# 09.net
KiCad netlist of a schematic drawn in Altium Designer
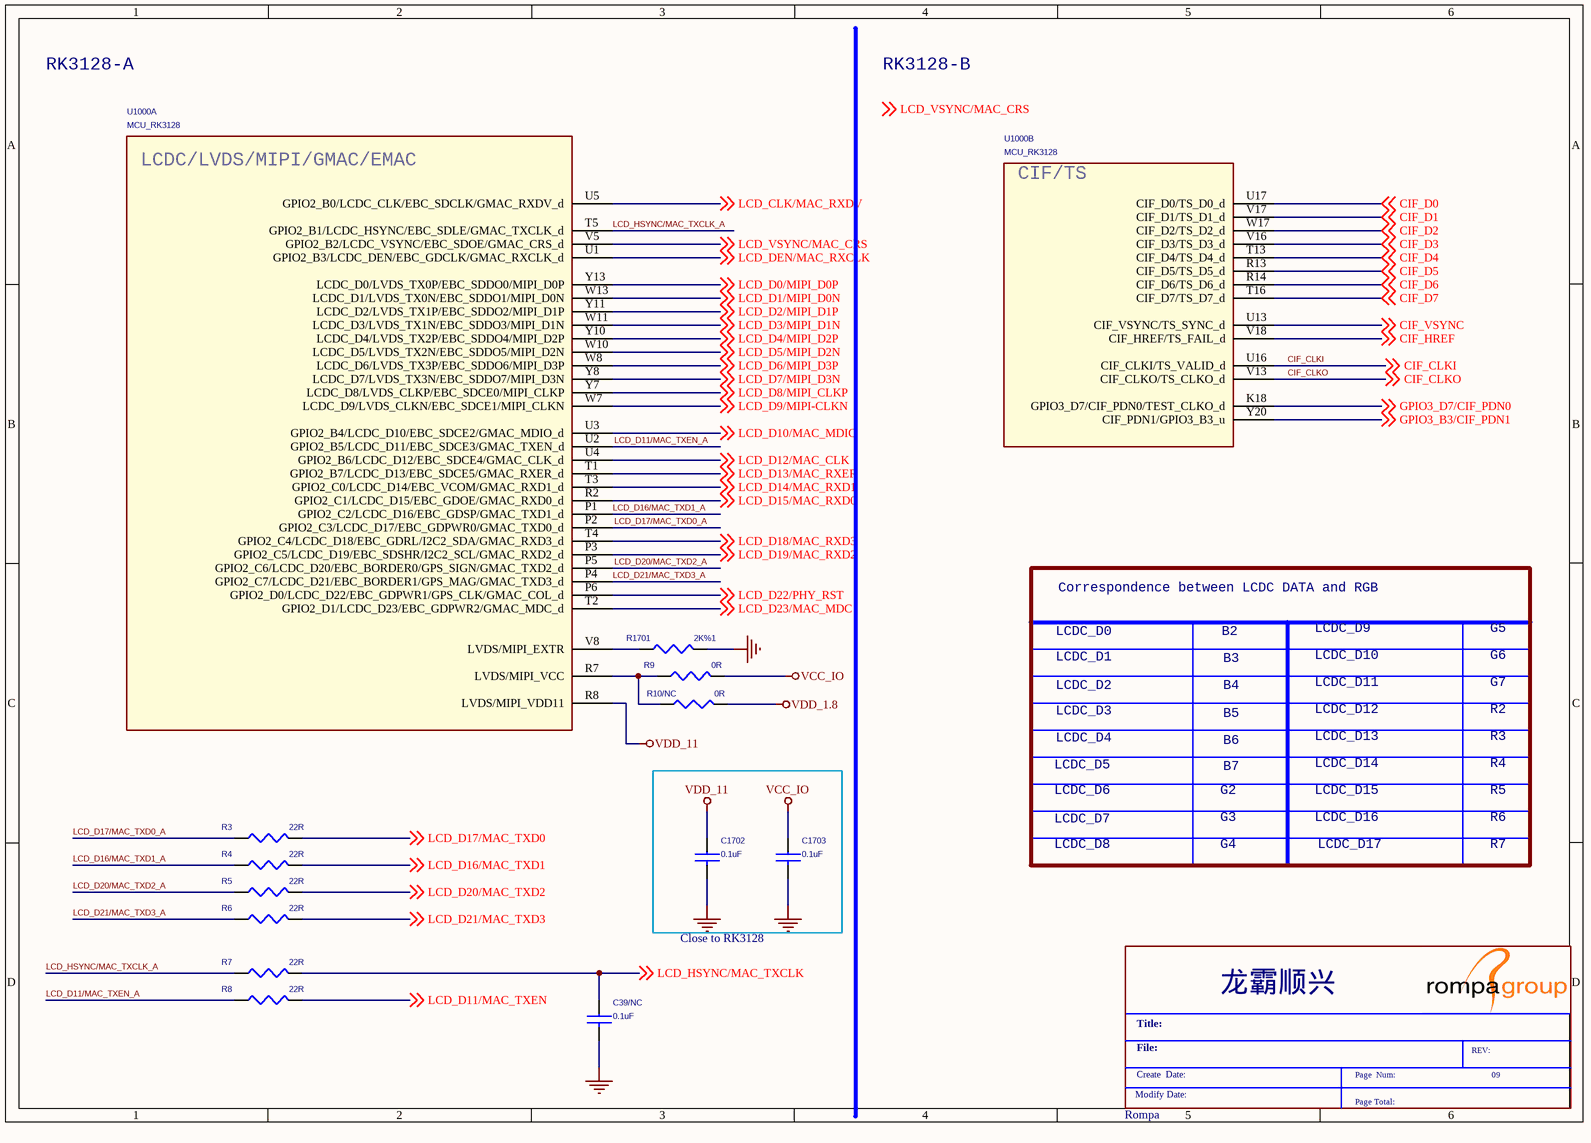
[diagram p0: 09.SchDoc]

(export (version "E")
  (design (tool "Eeschema 10.0.6"))
  (components
    (comp (ref "*")
      (value "Rompa")
      (fields (field (name "SCHEMATIC PAGE NUMBER") "09"))
      (libsource (lib "RK3128_BETA_V03_20151231_Library") (part "Rompa"))
    )
    (comp (ref "C39/NC")
      (value "0.1uF")
      (footprint "C0402")
      (description "RoHS CHIP CAP 0.1uF +10/-10% X7R")
      (libsource (lib "*") (part "CAP NP"))
    )
    (comp (ref "C1702")
      (value "0.1uF")
      (footprint "C0402")
      (description "RoHS CHIP CAP 0.1uF +10/-10% X7R")
      (libsource (lib "*") (part "CAP NP"))
    )
    (comp (ref "C1703")
      (value "0.1uF")
      (footprint "C0402")
      (description "RoHS CHIP CAP 0.1uF +10/-10% X7R")
      (libsource (lib "*") (part "CAP NP"))
    )
    (comp (ref "R3")
      (value "22R")
      (footprint "R0402")
      (description "ROHS CHIP RES 4.7K 1/16W 5%")
      (libsource (lib "*") (part "RES 1B"))
    )
    (comp (ref "R4")
      (value "22R")
      (footprint "R0402")
      (description "ROHS CHIP RES 4.7K 1/16W 5%")
      (libsource (lib "*") (part "RES 1B"))
    )
    (comp (ref "R5")
      (value "22R")
      (footprint "R0402")
      (description "ROHS CHIP RES 4.7K 1/16W 5%")
      (libsource (lib "*") (part "RES 1B"))
    )
    (comp (ref "R6")
      (value "22R")
      (footprint "R0402")
      (description "ROHS CHIP RES 4.7K 1/16W 5%")
      (libsource (lib "*") (part "RES 1B"))
    )
    (comp (ref "R7")
      (value "22R")
      (footprint "R0402")
      (description "ROHS CHIP RES 4.7K 1/16W 5%")
      (libsource (lib "*") (part "RES 1B"))
    )
    (comp (ref "R8")
      (value "22R")
      (footprint "R0402")
      (description "ROHS CHIP RES 4.7K 1/16W 5%")
      (libsource (lib "*") (part "RES 1B"))
    )
    (comp (ref "R9")
      (value "0R")
      (footprint "R0402")
      (description "ROHS CHIP RES 4.7K 1/16W 5%")
      (libsource (lib "*") (part "RES 1B"))
    )
    (comp (ref "R10/NC")
      (value "0R")
      (footprint "R0402")
      (description "NC/ 0R")
      (libsource (lib "*") (part "RES 1B"))
    )
    (comp (ref "R1701")
      (value "2K%1")
      (footprint "R0402")
      (description "ROHS CHIP RES 4.7K 1/16W 5%")
      (libsource (lib "*") (part "RES 1B"))
    )
    (comp (ref "U1000")
      (value "MCU_RK3128")
      (footprint "BGA316-14X14-0.65")
      (libsource (lib "*") (part "MCU_RK3128"))
    )
  )
  (nets
    (net (code "1") (name "/LCD_D11{slash}MAC_TXEN_A") (class "Default")
      (node (ref "R8") (pin "1") (pinfunction "1_1") (pintype "passive"))
      (node (ref "U1000") (pin "U2") (pinfunction "GPIO2_B5/LCDC_D11/EBC_SDCE3/GMAC_TXEN_d_U2") (pintype "passive"))
    )
    (net (code "2") (name "/LCD_D16{slash}MAC_TXD1_A") (class "Default")
      (node (ref "R4") (pin "1") (pinfunction "1_1") (pintype "passive"))
      (node (ref "U1000") (pin "P1") (pinfunction "GPIO2_C2/LCDC_D16/EBC_GDSP/GMAC_TXD1_d_P1") (pintype "passive"))
    )
    (net (code "3") (name "/LCD_D17{slash}MAC_TXD0_A") (class "Default")
      (node (ref "R3") (pin "1") (pinfunction "1_1") (pintype "passive"))
      (node (ref "U1000") (pin "P2") (pinfunction "GPIO2_C3/LCDC_D17/EBC_GDPWR0/GMAC_TXD0_d_P2") (pintype "passive"))
    )
    (net (code "4") (name "/LCD_D20{slash}MAC_TXD2_A") (class "Default")
      (node (ref "R5") (pin "1") (pinfunction "1_1") (pintype "passive"))
      (node (ref "U1000") (pin "P5") (pinfunction "GPIO2_C6/LCDC_D20/EBC_BORDER0/GPS_SIGN/GMAC_TXD2_d_P5") (pintype "passive"))
    )
    (net (code "5") (name "/LCD_D21{slash}MAC_TXD3_A") (class "Default")
      (node (ref "R6") (pin "1") (pinfunction "1_1") (pintype "passive"))
      (node (ref "U1000") (pin "P4") (pinfunction "GPIO2_C7/LCDC_D21/EBC_BORDER1/GPS_MAG/GMAC_TXD3_d_P4") (pintype "passive"))
    )
    (net (code "6") (name "/LCD_HSYNC{slash}MAC_TXCLK_A") (class "Default")
      (node (ref "R7") (pin "1") (pinfunction "1_1") (pintype "passive"))
      (node (ref "U1000") (pin "T5") (pinfunction "GPIO2_B1/LCDC_HSYNC/EBC_SDLE/GMAC_TXCLK_d_T5") (pintype "passive"))
    )
    (net (code "7") (name "CIF_CLKI") (class "Default")
      (node (ref "U1000") (pin "U16") (pinfunction "CIF_CLKI/TS_VALID_d_U16") (pintype "passive"))
    )
    (net (code "8") (name "CIF_CLKO") (class "Default")
      (node (ref "U1000") (pin "V13") (pinfunction "CIF_CLKO/TS_CLKO_d_V13") (pintype "passive"))
    )
    (net (code "9") (name "CIF_D0") (class "Default")
      (node (ref "U1000") (pin "U17") (pinfunction "CIF_D0/TS_D0_d_U17") (pintype "passive"))
    )
    (net (code "10") (name "CIF_D1") (class "Default")
      (node (ref "U1000") (pin "V17") (pinfunction "CIF_D1/TS_D1_d_V17") (pintype "passive"))
    )
    (net (code "11") (name "CIF_D2") (class "Default")
      (node (ref "U1000") (pin "W17") (pinfunction "CIF_D2/TS_D2_d_W17") (pintype "passive"))
    )
    (net (code "12") (name "CIF_D3") (class "Default")
      (node (ref "U1000") (pin "V16") (pinfunction "CIF_D3/TS_D3_d_V16") (pintype "passive"))
    )
    (net (code "13") (name "CIF_D4") (class "Default")
      (node (ref "U1000") (pin "T13") (pinfunction "CIF_D4/TS_D4_d_T13") (pintype "passive"))
    )
    (net (code "14") (name "CIF_D5") (class "Default")
      (node (ref "U1000") (pin "R13") (pinfunction "CIF_D5/TS_D5_d_R13") (pintype "passive"))
    )
    (net (code "15") (name "CIF_D6") (class "Default")
      (node (ref "U1000") (pin "R14") (pinfunction "CIF_D6/TS_D6_d_R14") (pintype "passive"))
    )
    (net (code "16") (name "CIF_D7") (class "Default")
      (node (ref "U1000") (pin "T16") (pinfunction "CIF_D7/TS_D7_d_T16") (pintype "passive"))
    )
    (net (code "17") (name "CIF_HREF") (class "Default")
      (node (ref "U1000") (pin "V18") (pinfunction "CIF_HREF/TS_FAIL_d_V18") (pintype "passive"))
    )
    (net (code "18") (name "CIF_VSYNC") (class "Default")
      (node (ref "U1000") (pin "U13") (pinfunction "CIF_VSYNC/TS_SYNC_d_U13") (pintype "passive"))
    )
    (net (code "19") (name "GND") (class "Default")
      (node (ref "C1702") (pin "2") (pinfunction "2_2") (pintype "passive"))
      (node (ref "C1703") (pin "2") (pinfunction "2_2") (pintype "passive"))
      (node (ref "C39/NC") (pin "2") (pinfunction "2_2") (pintype "passive"))
      (node (ref "R1701") (pin "2") (pinfunction "2_2") (pintype "passive"))
    )
    (net (code "20") (name "GPIO3_B3{slash}CIF_PDN1") (class "Default")
      (node (ref "U1000") (pin "Y20") (pinfunction "CIF_PDN1/GPIO3_B3_u_Y20") (pintype "passive"))
    )
    (net (code "21") (name "GPIO3_D7{slash}CIF_PDN0") (class "Default")
      (node (ref "U1000") (pin "K18") (pinfunction "GPIO3_D7/CIF_PDN0/TEST_CLKO_d_K18") (pintype "passive"))
    )
    (net (code "22") (name "LCD_CLK{slash}MAC_RXDV") (class "Default")
      (node (ref "U1000") (pin "U5") (pinfunction "GPIO2_B0/LCDC_CLK/EBC_SDCLK/GMAC_RXDV_d_U5") (pintype "passive"))
    )
    (net (code "23") (name "LCD_D0{slash}MIPI_D0P") (class "Default")
      (node (ref "U1000") (pin "Y13") (pinfunction "LCDC_D0/LVDS_TX0P/EBC_SDDO0/MIPI_D0P_Y13") (pintype "passive"))
    )
    (net (code "24") (name "LCD_D1{slash}MIPI_D0N") (class "Default")
      (node (ref "U1000") (pin "W13") (pinfunction "LCDC_D1/LVDS_TX0N/EBC_SDDO1/MIPI_D0N_W13") (pintype "passive"))
    )
    (net (code "25") (name "LCD_D2{slash}MIPI_D1P") (class "Default")
      (node (ref "U1000") (pin "Y11") (pinfunction "LCDC_D2/LVDS_TX1P/EBC_SDDO2/MIPI_D1P_Y11") (pintype "passive"))
    )
    (net (code "26") (name "LCD_D3{slash}MIPI_D1N") (class "Default")
      (node (ref "U1000") (pin "W11") (pinfunction "LCDC_D3/LVDS_TX1N/EBC_SDDO3/MIPI_D1N_W11") (pintype "passive"))
    )
    (net (code "27") (name "LCD_D4{slash}MIPI_D2P") (class "Default")
      (node (ref "U1000") (pin "Y10") (pinfunction "LCDC_D4/LVDS_TX2P/EBC_SDDO4/MIPI_D2P_Y10") (pintype "passive"))
    )
    (net (code "28") (name "LCD_D5{slash}MIPI_D2N") (class "Default")
      (node (ref "U1000") (pin "W10") (pinfunction "LCDC_D5/LVDS_TX2N/EBC_SDDO5/MIPI_D2N_W10") (pintype "passive"))
    )
    (net (code "29") (name "LCD_D6{slash}MIPI_D3P") (class "Default")
      (node (ref "U1000") (pin "W8") (pinfunction "LCDC_D6/LVDS_TX3P/EBC_SDDO6/MIPI_D3P_W8") (pintype "passive"))
    )
    (net (code "30") (name "LCD_D7{slash}MIPI_D3N") (class "Default")
      (node (ref "U1000") (pin "Y8") (pinfunction "LCDC_D7/LVDS_TX3N/EBC_SDDO7/MIPI_D3N_Y8") (pintype "passive"))
    )
    (net (code "31") (name "LCD_D8{slash}MIPI_CLKP") (class "Default")
      (node (ref "U1000") (pin "Y7") (pinfunction "LCDC_D8/LVDS_CLKP/EBC_SDCE0/MIPI_CLKP_Y7") (pintype "passive"))
    )
    (net (code "32") (name "LCD_D9{slash}MIPI-CLKN") (class "Default")
      (node (ref "U1000") (pin "W7") (pinfunction "LCDC_D9/LVDS_CLKN/EBC_SDCE1/MIPI_CLKN_W7") (pintype "passive"))
    )
    (net (code "33") (name "LCD_D10{slash}MAC_MDIO") (class "Default")
      (node (ref "U1000") (pin "U3") (pinfunction "GPIO2_B4/LCDC_D10/EBC_SDCE2/GMAC_MDIO_d_U3") (pintype "passive"))
    )
    (net (code "34") (name "LCD_D11{slash}MAC_TXEN") (class "Default")
      (node (ref "R8") (pin "2") (pinfunction "2_2") (pintype "passive"))
    )
    (net (code "35") (name "LCD_D12{slash}MAC_CLK") (class "Default")
      (node (ref "U1000") (pin "U4") (pinfunction "GPIO2_B6/LCDC_D12/EBC_SDCE4/GMAC_CLK_d_U4") (pintype "passive"))
    )
    (net (code "36") (name "LCD_D13{slash}MAC_RXER") (class "Default")
      (node (ref "U1000") (pin "T1") (pinfunction "GPIO2_B7/LCDC_D13/EBC_SDCE5/GMAC_RXER_d_T1") (pintype "passive"))
    )
    (net (code "37") (name "LCD_D14{slash}MAC_RXD1") (class "Default")
      (node (ref "U1000") (pin "T3") (pinfunction "GPIO2_C0/LCDC_D14/EBC_VCOM/GMAC_RXD1_d_T3") (pintype "passive"))
    )
    (net (code "38") (name "LCD_D15{slash}MAC_RXD0") (class "Default")
      (node (ref "U1000") (pin "R2") (pinfunction "GPIO2_C1/LCDC_D15/EBC_GDOE/GMAC_RXD0_d_R2") (pintype "passive"))
    )
    (net (code "39") (name "LCD_D16{slash}MAC_TXD1") (class "Default")
      (node (ref "R4") (pin "2") (pinfunction "2_2") (pintype "passive"))
    )
    (net (code "40") (name "LCD_D17{slash}MAC_TXD0") (class "Default")
      (node (ref "R3") (pin "2") (pinfunction "2_2") (pintype "passive"))
    )
    (net (code "41") (name "LCD_D18{slash}MAC_RXD3") (class "Default")
      (node (ref "U1000") (pin "T4") (pinfunction "GPIO2_C4/LCDC_D18/EBC_GDRL/I2C2_SDA/GMAC_RXD3_d_T4") (pintype "passive"))
    )
    (net (code "42") (name "LCD_D19{slash}MAC_RXD2") (class "Default")
      (node (ref "U1000") (pin "P3") (pinfunction "GPIO2_C5/LCDC_D19/EBC_SDSHR/I2C2_SCL/GMAC_RXD2_d_P3") (pintype "passive"))
    )
    (net (code "43") (name "LCD_D20{slash}MAC_TXD2") (class "Default")
      (node (ref "R5") (pin "2") (pinfunction "2_2") (pintype "passive"))
    )
    (net (code "44") (name "LCD_D21{slash}MAC_TXD3") (class "Default")
      (node (ref "R6") (pin "2") (pinfunction "2_2") (pintype "passive"))
    )
    (net (code "45") (name "LCD_D22{slash}PHY_RST") (class "Default")
      (node (ref "U1000") (pin "P6") (pinfunction "GPIO2_D0/LCDC_D22/EBC_GDPWR1/GPS_CLK/GMAC_COL_d_P6") (pintype "passive"))
    )
    (net (code "46") (name "LCD_D23{slash}MAC_MDC") (class "Default")
      (node (ref "U1000") (pin "T2") (pinfunction "GPIO2_D1/LCDC_D23/EBC_GDPWR2/GMAC_MDC_d_T2") (pintype "passive"))
    )
    (net (code "47") (name "LCD_DEN{slash}MAC_RXCLK") (class "Default")
      (node (ref "U1000") (pin "U1") (pinfunction "GPIO2_B3/LCDC_DEN/EBC_GDCLK/GMAC_RXCLK_d_U1") (pintype "passive"))
    )
    (net (code "48") (name "LCD_HSYNC{slash}MAC_TXCLK") (class "Default")
      (node (ref "C39/NC") (pin "1") (pinfunction "1_1") (pintype "passive"))
      (node (ref "R7") (pin "2") (pinfunction "2_2") (pintype "passive"))
    )
    (net (code "49") (name "LCD_VSYNC{slash}MAC_CRS") (class "Default")
      (node (ref "U1000") (pin "V5") (pinfunction "GPIO2_B2/LCDC_VSYNC/EBC_SDOE/GMAC_CRS_d_V5") (pintype "passive"))
    )
    (net (code "50") (name "Net-(U1000A-LVDS{slash}MIPI_EXTR)") (class "Default")
      (node (ref "R1701") (pin "1") (pinfunction "1_1") (pintype "passive"))
      (node (ref "U1000") (pin "V8") (pinfunction "LVDS/MIPI_EXTR_V8") (pintype "passive"))
    )
    (net (code "51") (name "Net-(U1000A-LVDS{slash}MIPI_VCC)") (class "Default")
      (node (ref "R10/NC") (pin "1") (pinfunction "1_1") (pintype "passive"))
      (node (ref "R9") (pin "1") (pinfunction "1_1") (pintype "passive"))
      (node (ref "U1000") (pin "R7") (pinfunction "LVDS/MIPI_VCC_R7") (pintype "passive"))
    )
    (net (code "52") (name "VCC_IO") (class "Default")
      (node (ref "C1703") (pin "1") (pinfunction "1_1") (pintype "passive"))
      (node (ref "R9") (pin "2") (pinfunction "2_2") (pintype "passive"))
    )
    (net (code "53") (name "VDD_1.8") (class "Default")
      (node (ref "R10/NC") (pin "2") (pinfunction "2_2") (pintype "passive"))
    )
    (net (code "54") (name "VDD_11") (class "Default")
      (node (ref "C1702") (pin "1") (pinfunction "1_1") (pintype "passive"))
      (node (ref "U1000") (pin "R8") (pinfunction "LVDS/MIPI_VDD11_R8") (pintype "passive"))
    )
  )
)
